# LED.net
KiCad netlist of a schematic drawn in Altium Designer
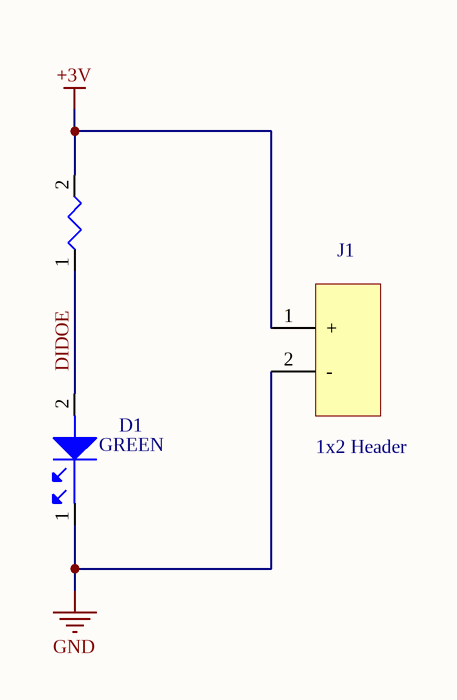
[diagram p0: LED.SchDoc]

(export (version "E")
  (design (tool "Eeschema 10.0.6"))
  (components
    (comp (ref "D1")
      (value "GREEN")
      (footprint "LED0603G")
      (description "Standard LEDs - SMD LED GR HI-BRT USS")
      (fields
        (field (name "MANUFACTURER") "Panasonic SSG")
        (field (name "MANUFACTURER PART NUMBER") "LNJ337W83RA")
      )
      (libsource (lib "LED_Schlib") (part "LNJ337W83RA"))
    )
    (comp (ref "J1")
      (value "1x2 Header")
      (footprint "HDR1x2")
      (description "KK 254 Wire-to-Board Header, Vertical, with Friction Lock, 2 Circuits, Gold (Au) Plating")
      (fields (field (name "MANUFACTURER") "Molex") (field (name "MANUFACTURER PART NUMBER") "0022292021"))
      (libsource (lib "LED_Schlib") (part "0022292021"))
    )
    (comp (ref "R1")
      (value "360R")
      (footprint "R0805")
      (description "SMD Chip Resistor, 360 Ohm, ± 1%, 125 mW, 0805 [2012 Metric], Thick Film, General Purpose")
      (fields
        (field (name "MANUFACTURER") "Vishay")
        (field (name "MANUFACTURER PART NUMBER") "CRCW0805360RFKEA")
      )
      (libsource (lib "LED_Schlib") (part "CRCW0805360RFKEA"))
    )
  )
  (nets
    (net (code "1") (name "+3V") (class "Default")
      (node (ref "J1") (pin "1") (pinfunction "+_1") (pintype "passive"))
      (node (ref "R1") (pin "2") (pinfunction "2_2") (pintype "passive"))
    )
    (net (code "2") (name "/DIDOE") (class "Default")
      (node (ref "D1") (pin "2") (pinfunction "2_2") (pintype "passive"))
      (node (ref "R1") (pin "1") (pinfunction "1_1") (pintype "passive"))
    )
    (net (code "3") (name "GND") (class "Default")
      (node (ref "D1") (pin "1") (pinfunction "1_1") (pintype "passive"))
      (node (ref "J1") (pin "2") (pinfunction "-_2") (pintype "passive"))
    )
  )
)
